# CONN.net
KiCad netlist of a schematic drawn in Altium Designer
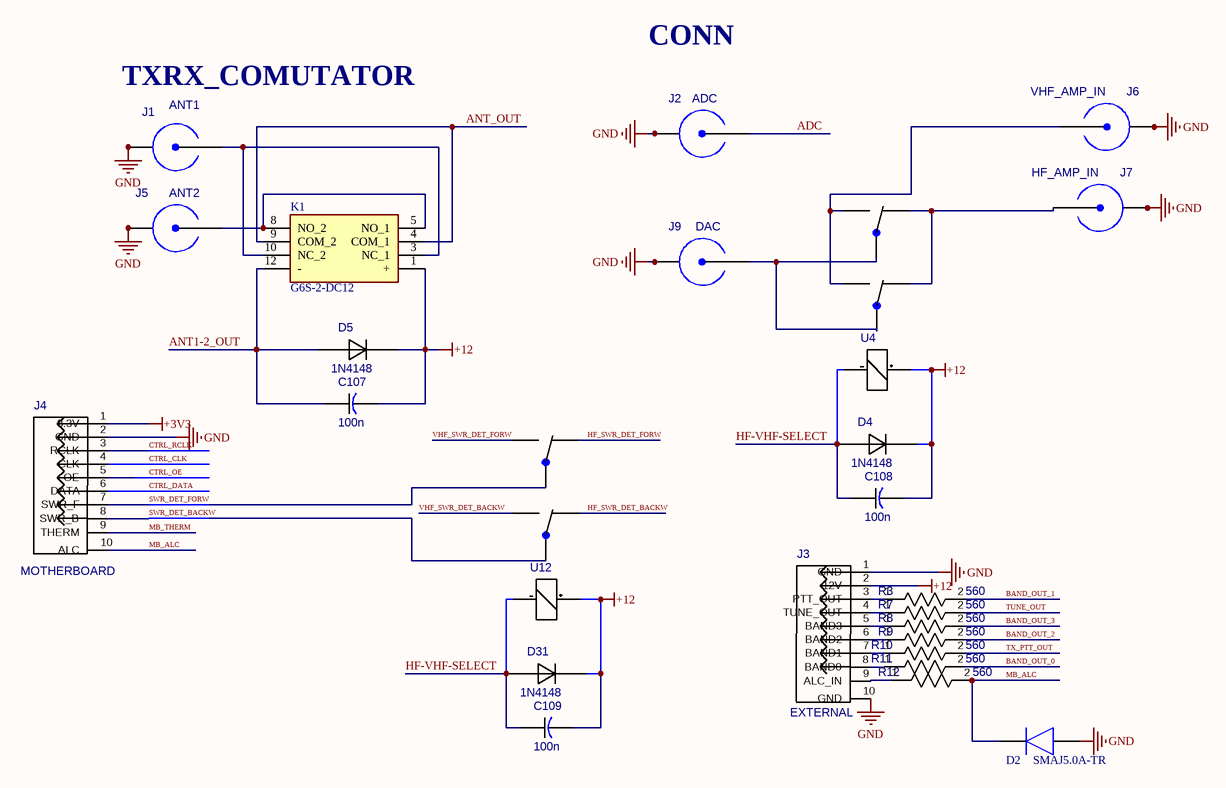
[diagram p0: CONN.SchDoc]

(export (version "E")
  (design (tool "Eeschema 10.0.6"))
  (components
    (comp (ref "C107")
      (value "100n")
      (footprint "CAP_0805")
      (description "CAP_0805")
      (libsource (lib "*") (part "CAP_0805"))
    )
    (comp (ref "C108")
      (value "100n")
      (footprint "CAP_0805")
      (description "CAP_0805")
      (libsource (lib "*") (part "CAP_0805"))
    )
    (comp (ref "C109")
      (value "100n")
      (footprint "CAP_0805")
      (description "CAP_0805")
      (libsource (lib "*") (part "CAP_0805"))
    )
    (comp (ref "D2")
      (value "SMAJ5.0A-TR")
      (footprint "SMBJ36CATR")
      (description "Diode")
      (fields
        (field (name "MANUFACTURER_PART_NUMBER") "SMLVT3V3")
        (field (name "MOUSER PART NUMBER") "511-SMLVT3V3")
      )
      (libsource (lib "RF-UNIT-BIG") (part "SMLVT3V3"))
    )
    (comp (ref "D4") (value "1N4148") (footprint "SS14") (libsource (lib "RF-UNIT-BIG") (part "1N4148")))
    (comp (ref "D5") (value "1N4148") (footprint "SS14") (libsource (lib "RF-UNIT-BIG") (part "1N4148")))
    (comp (ref "D31") (value "1N4148") (footprint "SS14") (libsource (lib "RF-UNIT-BIG") (part "1N4148")))
    (comp (ref "J1")
      (value "ANT1")
      (footprint "31-5431")
      (description "SMA")
      (libsource (lib "") (part "31-5431_1"))
    )
    (comp (ref "J2")
      (value "ADC")
      (footprint "31-5431")
      (description "SMA")
      (libsource (lib "") (part "31-5431_1"))
    )
    (comp (ref "J3")
      (value "EXTERNAL")
      (footprint "90131-0126")
      (description "2*5 PIN")
      (libsource (lib "RF-UNIT") (part "90131-0126"))
    )
    (comp (ref "J4")
      (value "MOTHERBOARD")
      (footprint "90131-0126")
      (description "2*5 PIN")
      (libsource (lib "RF-UNIT") (part "90131-0126"))
    )
    (comp (ref "J5")
      (value "ANT2")
      (footprint "31-5431")
      (description "SMA")
      (libsource (lib "") (part "31-5431_1"))
    )
    (comp (ref "J6")
      (value "VHF_AMP_IN")
      (footprint "31-5431")
      (description "SMA")
      (libsource (lib "RF-UNIT_1") (part "31-5431"))
    )
    (comp (ref "J7")
      (value "HF_AMP_IN")
      (footprint "31-5431")
      (description "SMA")
      (libsource (lib "RF-UNIT_1") (part "31-5431"))
    )
    (comp (ref "J9")
      (value "DAC")
      (footprint "31-5431")
      (description "SMA")
      (libsource (lib "") (part "31-5431_1"))
    )
    (comp (ref "K1")
      (value "G6S-2-DC12")
      (footprint "G6S2DC12")
      (description "Relay or Contactor")
      (fields (field (name "MOUSER PART NUMBER") "653-G6S-2-DC12A"))
      (libsource (lib "*") (part "G6S-2-DC12"))
    )
    (comp (ref "R3")
      (value "560")
      (footprint "RES_0805")
      (description "RES_0805")
      (libsource (lib "*") (part "RES_0805"))
    )
    (comp (ref "R7")
      (value "560")
      (footprint "RES_0805")
      (description "RES_0805")
      (libsource (lib "*") (part "RES_0805"))
    )
    (comp (ref "R8")
      (value "560")
      (footprint "RES_0805")
      (description "RES_0805")
      (libsource (lib "*") (part "RES_0805"))
    )
    (comp (ref "R9")
      (value "560")
      (footprint "RES_0805")
      (description "RES_0805")
      (libsource (lib "*") (part "RES_0805"))
    )
    (comp (ref "R10")
      (value "560")
      (footprint "RES_0805")
      (description "RES_0805")
      (libsource (lib "*") (part "RES_0805"))
    )
    (comp (ref "R11")
      (value "560")
      (footprint "RES_0805")
      (description "RES_0805")
      (libsource (lib "*") (part "RES_0805"))
    )
    (comp (ref "R12")
      (value "560")
      (footprint "RES_0805")
      (description "RES_0805")
      (libsource (lib "*") (part "RES_0805"))
    )
    (comp (ref "U4")
      (value "Axicom IM06")
      (footprint "IM06GR")
      (libsource (lib "RF-UNIT-BIG") (part "Axicom IM06"))
    )
    (comp (ref "U12")
      (value "Axicom IM06")
      (footprint "IM06GR")
      (libsource (lib "RF-UNIT-BIG") (part "Axicom IM06"))
    )
  )
  (nets
    (net (code "1") (name "+3V3") (class "Default")
      (node (ref "J4") (pin "1") (pinfunction "3.3V_1") (pintype "passive"))
    )
    (net (code "2") (name "+12") (class "Default")
      (node (ref "C107") (pin "2") (pinfunction "2_2") (pintype "passive"))
      (node (ref "C108") (pin "2") (pinfunction "2_2") (pintype "passive"))
      (node (ref "C109") (pin "2") (pinfunction "2_2") (pintype "passive"))
      (node (ref "D31") (pin "1") (pinfunction "K_1") (pintype "passive"))
      (node (ref "D4") (pin "1") (pinfunction "K_1") (pintype "passive"))
      (node (ref "D5") (pin "1") (pinfunction "K_1") (pintype "passive"))
      (node (ref "J3") (pin "2") (pinfunction "GND_2") (pintype "passive"))
      (node (ref "K1") (pin "1") (pinfunction "+_1") (pintype "passive"))
      (node (ref "U12") (pin "1") (pinfunction "+_1") (pintype "passive"))
      (node (ref "U4") (pin "1") (pinfunction "+_1") (pintype "passive"))
    )
    (net (code "4") (name "/ADC") (class "Default")
      (node (ref "J2") (pin "5") (pinfunction "CON_5") (pintype "passive"))
    )
    (net (code "5") (name "/ANT1-2_OUT") (class "Default")
      (node (ref "C107") (pin "1") (pinfunction "1_1") (pintype "passive"))
      (node (ref "D5") (pin "2") (pinfunction "A_2") (pintype "passive"))
      (node (ref "K1") (pin "12") (pinfunction "-_12") (pintype "passive"))
    )
    (net (code "6") (name "/ANT_OUT") (class "Default")
      (node (ref "K1") (pin "4") (pinfunction "COM_1_4") (pintype "passive"))
      (node (ref "K1") (pin "9") (pinfunction "COM_2_9") (pintype "passive"))
    )
    (net (code "7") (name "/BAND_OUT_0") (class "Default")
      (node (ref "R11") (pin "2") (pinfunction "2_2") (pintype "passive"))
    )
    (net (code "8") (name "/BAND_OUT_1") (class "Default")
      (node (ref "R3") (pin "2") (pinfunction "2_2") (pintype "passive"))
    )
    (net (code "9") (name "/BAND_OUT_2") (class "Default")
      (node (ref "R9") (pin "2") (pinfunction "2_2") (pintype "passive"))
    )
    (net (code "10") (name "/BAND_OUT_3") (class "Default")
      (node (ref "R8") (pin "2") (pinfunction "2_2") (pintype "passive"))
    )
    (net (code "11") (name "/CTRL_CLK") (class "Default")
      (node (ref "J4") (pin "4") (pinfunction "CLK_4") (pintype "passive"))
    )
    (net (code "12") (name "/CTRL_DATA") (class "Default")
      (node (ref "J4") (pin "6") (pinfunction "DATA_6") (pintype "passive"))
    )
    (net (code "13") (name "/CTRL_OE") (class "Default")
      (node (ref "J4") (pin "5") (pinfunction "OE_5") (pintype "passive"))
    )
    (net (code "14") (name "/CTRL_RCLK") (class "Default")
      (node (ref "J4") (pin "3") (pinfunction "RCLK_3") (pintype "passive"))
    )
    (net (code "15") (name "/HF-VHF-SELECT") (class "Default")
      (node (ref "C108") (pin "1") (pinfunction "1_1") (pintype "passive"))
      (node (ref "C109") (pin "1") (pinfunction "1_1") (pintype "passive"))
      (node (ref "D31") (pin "2") (pinfunction "A_2") (pintype "passive"))
      (node (ref "D4") (pin "2") (pinfunction "A_2") (pintype "passive"))
      (node (ref "U12") (pin "8") (pinfunction "-_8") (pintype "passive"))
      (node (ref "U4") (pin "8") (pinfunction "-_8") (pintype "passive"))
    )
    (net (code "16") (name "/HF_SWR_DET_BACKW") (class "Default")
      (node (ref "U12") (pin "2") (pinfunction "O_2") (pintype "passive"))
    )
    (net (code "17") (name "/HF_SWR_DET_FORW") (class "Default")
      (node (ref "U12") (pin "7") (pinfunction "O_7") (pintype "passive"))
    )
    (net (code "18") (name "/MB_ALC") (class "Default")
      (node (ref "D2") (pin "1") (pinfunction "K_1") (pintype "passive"))
      (node (ref "J4") (pin "10") (pinfunction "ALC_10") (pintype "passive"))
      (node (ref "R12") (pin "2") (pinfunction "2_2") (pintype "passive"))
    )
    (net (code "19") (name "/MB_THERM") (class "Default")
      (node (ref "J4") (pin "9") (pinfunction "THERM_9") (pintype "passive"))
    )
    (net (code "20") (name "/SWR_DET_BACKW") (class "Default")
      (node (ref "J4") (pin "8") (pinfunction "SWR_B_8") (pintype "passive"))
      (node (ref "U12") (pin "3") (pinfunction "P_3") (pintype "passive"))
    )
    (net (code "21") (name "/SWR_DET_FORW") (class "Default")
      (node (ref "J4") (pin "7") (pinfunction "SWR_F_7") (pintype "passive"))
      (node (ref "U12") (pin "6") (pinfunction "P_6") (pintype "passive"))
    )
    (net (code "22") (name "/TUNE_OUT") (class "Default")
      (node (ref "R7") (pin "2") (pinfunction "2_2") (pintype "passive"))
    )
    (net (code "23") (name "/TX_PTT_OUT") (class "Default")
      (node (ref "R10") (pin "2") (pinfunction "2_2") (pintype "passive"))
    )
    (net (code "24") (name "/VHF_SWR_DET_BACKW") (class "Default")
      (node (ref "U12") (pin "4") (pinfunction "S_4") (pintype "passive"))
    )
    (net (code "25") (name "/VHF_SWR_DET_FORW") (class "Default")
      (node (ref "U12") (pin "5") (pinfunction "S_5") (pintype "passive"))
    )
    (net (code "26") (name "GND") (class "Default")
      (node (ref "D2") (pin "2") (pinfunction "A_2") (pintype "passive"))
      (node (ref "J1") (pin "1") (pinfunction "GND_1") (pintype "passive"))
      (node (ref "J1") (pin "2") (pinfunction "GND_2") (pintype "passive"))
      (node (ref "J1") (pin "3") (pinfunction "GND_3") (pintype "passive"))
      (node (ref "J1") (pin "4") (pinfunction "GND_4") (pintype "passive"))
      (node (ref "J2") (pin "1") (pinfunction "GND_1") (pintype "passive"))
      (node (ref "J2") (pin "2") (pinfunction "GND_2") (pintype "passive"))
      (node (ref "J2") (pin "3") (pinfunction "GND_3") (pintype "passive"))
      (node (ref "J2") (pin "4") (pinfunction "GND_4") (pintype "passive"))
      (node (ref "J3") (pin "1") (pinfunction "3.3V_1") (pintype "passive"))
      (node (ref "J3") (pin "10") (pinfunction "ALC_10") (pintype "passive"))
      (node (ref "J4") (pin "2") (pinfunction "GND_2") (pintype "passive"))
      (node (ref "J5") (pin "1") (pinfunction "GND_1") (pintype "passive"))
      (node (ref "J5") (pin "2") (pinfunction "GND_2") (pintype "passive"))
      (node (ref "J5") (pin "3") (pinfunction "GND_3") (pintype "passive"))
      (node (ref "J5") (pin "4") (pinfunction "GND_4") (pintype "passive"))
      (node (ref "J6") (pin "1") (pinfunction "GND_1") (pintype "passive"))
      (node (ref "J6") (pin "2") (pinfunction "GND_2") (pintype "passive"))
      (node (ref "J6") (pin "3") (pinfunction "GND_3") (pintype "passive"))
      (node (ref "J6") (pin "4") (pinfunction "GND_4") (pintype "passive"))
      (node (ref "J7") (pin "1") (pinfunction "GND_1") (pintype "passive"))
      (node (ref "J7") (pin "2") (pinfunction "GND_2") (pintype "passive"))
      (node (ref "J7") (pin "3") (pinfunction "GND_3") (pintype "passive"))
      (node (ref "J7") (pin "4") (pinfunction "GND_4") (pintype "passive"))
      (node (ref "J9") (pin "1") (pinfunction "GND_1") (pintype "passive"))
      (node (ref "J9") (pin "2") (pinfunction "GND_2") (pintype "passive"))
      (node (ref "J9") (pin "3") (pinfunction "GND_3") (pintype "passive"))
      (node (ref "J9") (pin "4") (pinfunction "GND_4") (pintype "passive"))
    )
    (net (code "27") (name "Net-(J1-CON)") (class "Default")
      (node (ref "J1") (pin "5") (pinfunction "CON_5") (pintype "passive"))
      (node (ref "K1") (pin "10") (pinfunction "NC_2_10") (pintype "passive"))
      (node (ref "K1") (pin "3") (pinfunction "NC_1_3") (pintype "passive"))
    )
    (net (code "28") (name "Net-(J3-CLK)") (class "Default")
      (node (ref "J3") (pin "4") (pinfunction "CLK_4") (pintype "passive"))
      (node (ref "R7") (pin "1") (pinfunction "1_1") (pintype "passive"))
    )
    (net (code "29") (name "Net-(J3-DATA)") (class "Default")
      (node (ref "J3") (pin "6") (pinfunction "DATA_6") (pintype "passive"))
      (node (ref "R9") (pin "1") (pinfunction "1_1") (pintype "passive"))
    )
    (net (code "30") (name "Net-(J3-OE)") (class "Default")
      (node (ref "J3") (pin "5") (pinfunction "OE_5") (pintype "passive"))
      (node (ref "R8") (pin "1") (pinfunction "1_1") (pintype "passive"))
    )
    (net (code "31") (name "Net-(J3-RCLK)") (class "Default")
      (node (ref "J3") (pin "3") (pinfunction "RCLK_3") (pintype "passive"))
      (node (ref "R3") (pin "1") (pinfunction "1_1") (pintype "passive"))
    )
    (net (code "32") (name "Net-(J3-SWR_B)") (class "Default")
      (node (ref "J3") (pin "8") (pinfunction "SWR_B_8") (pintype "passive"))
      (node (ref "R11") (pin "1") (pinfunction "1_1") (pintype "passive"))
    )
    (net (code "33") (name "Net-(J3-SWR_F)") (class "Default")
      (node (ref "J3") (pin "7") (pinfunction "SWR_F_7") (pintype "passive"))
      (node (ref "R10") (pin "1") (pinfunction "1_1") (pintype "passive"))
    )
    (net (code "34") (name "Net-(J3-THERM)") (class "Default")
      (node (ref "J3") (pin "9") (pinfunction "THERM_9") (pintype "passive"))
      (node (ref "R12") (pin "1") (pinfunction "1_1") (pintype "passive"))
    )
    (net (code "35") (name "Net-(J5-CON)") (class "Default")
      (node (ref "J5") (pin "5") (pinfunction "CON_5") (pintype "passive"))
      (node (ref "K1") (pin "5") (pinfunction "NO_1_5") (pintype "passive"))
      (node (ref "K1") (pin "8") (pinfunction "NO_2_8") (pintype "passive"))
    )
    (net (code "36") (name "Net-(J6-CON)") (class "Default")
      (node (ref "J6") (pin "5") (pinfunction "CON_5") (pintype "passive"))
      (node (ref "U4") (pin "4") (pinfunction "S_4") (pintype "passive"))
      (node (ref "U4") (pin "5") (pinfunction "S_5") (pintype "passive"))
    )
    (net (code "37") (name "Net-(J7-CON)") (class "Default")
      (node (ref "J7") (pin "5") (pinfunction "CON_5") (pintype "passive"))
      (node (ref "U4") (pin "2") (pinfunction "O_2") (pintype "passive"))
      (node (ref "U4") (pin "7") (pinfunction "O_7") (pintype "passive"))
    )
    (net (code "38") (name "Net-(J9-CON)") (class "Default")
      (node (ref "J9") (pin "5") (pinfunction "CON_5") (pintype "passive"))
      (node (ref "U4") (pin "3") (pinfunction "P_3") (pintype "passive"))
      (node (ref "U4") (pin "6") (pinfunction "P_6") (pintype "passive"))
    )
  )
)
